# SCH_Moses-Mini_2025-01-24.net
KiCad netlist of a schematic drawn in EasyEDA
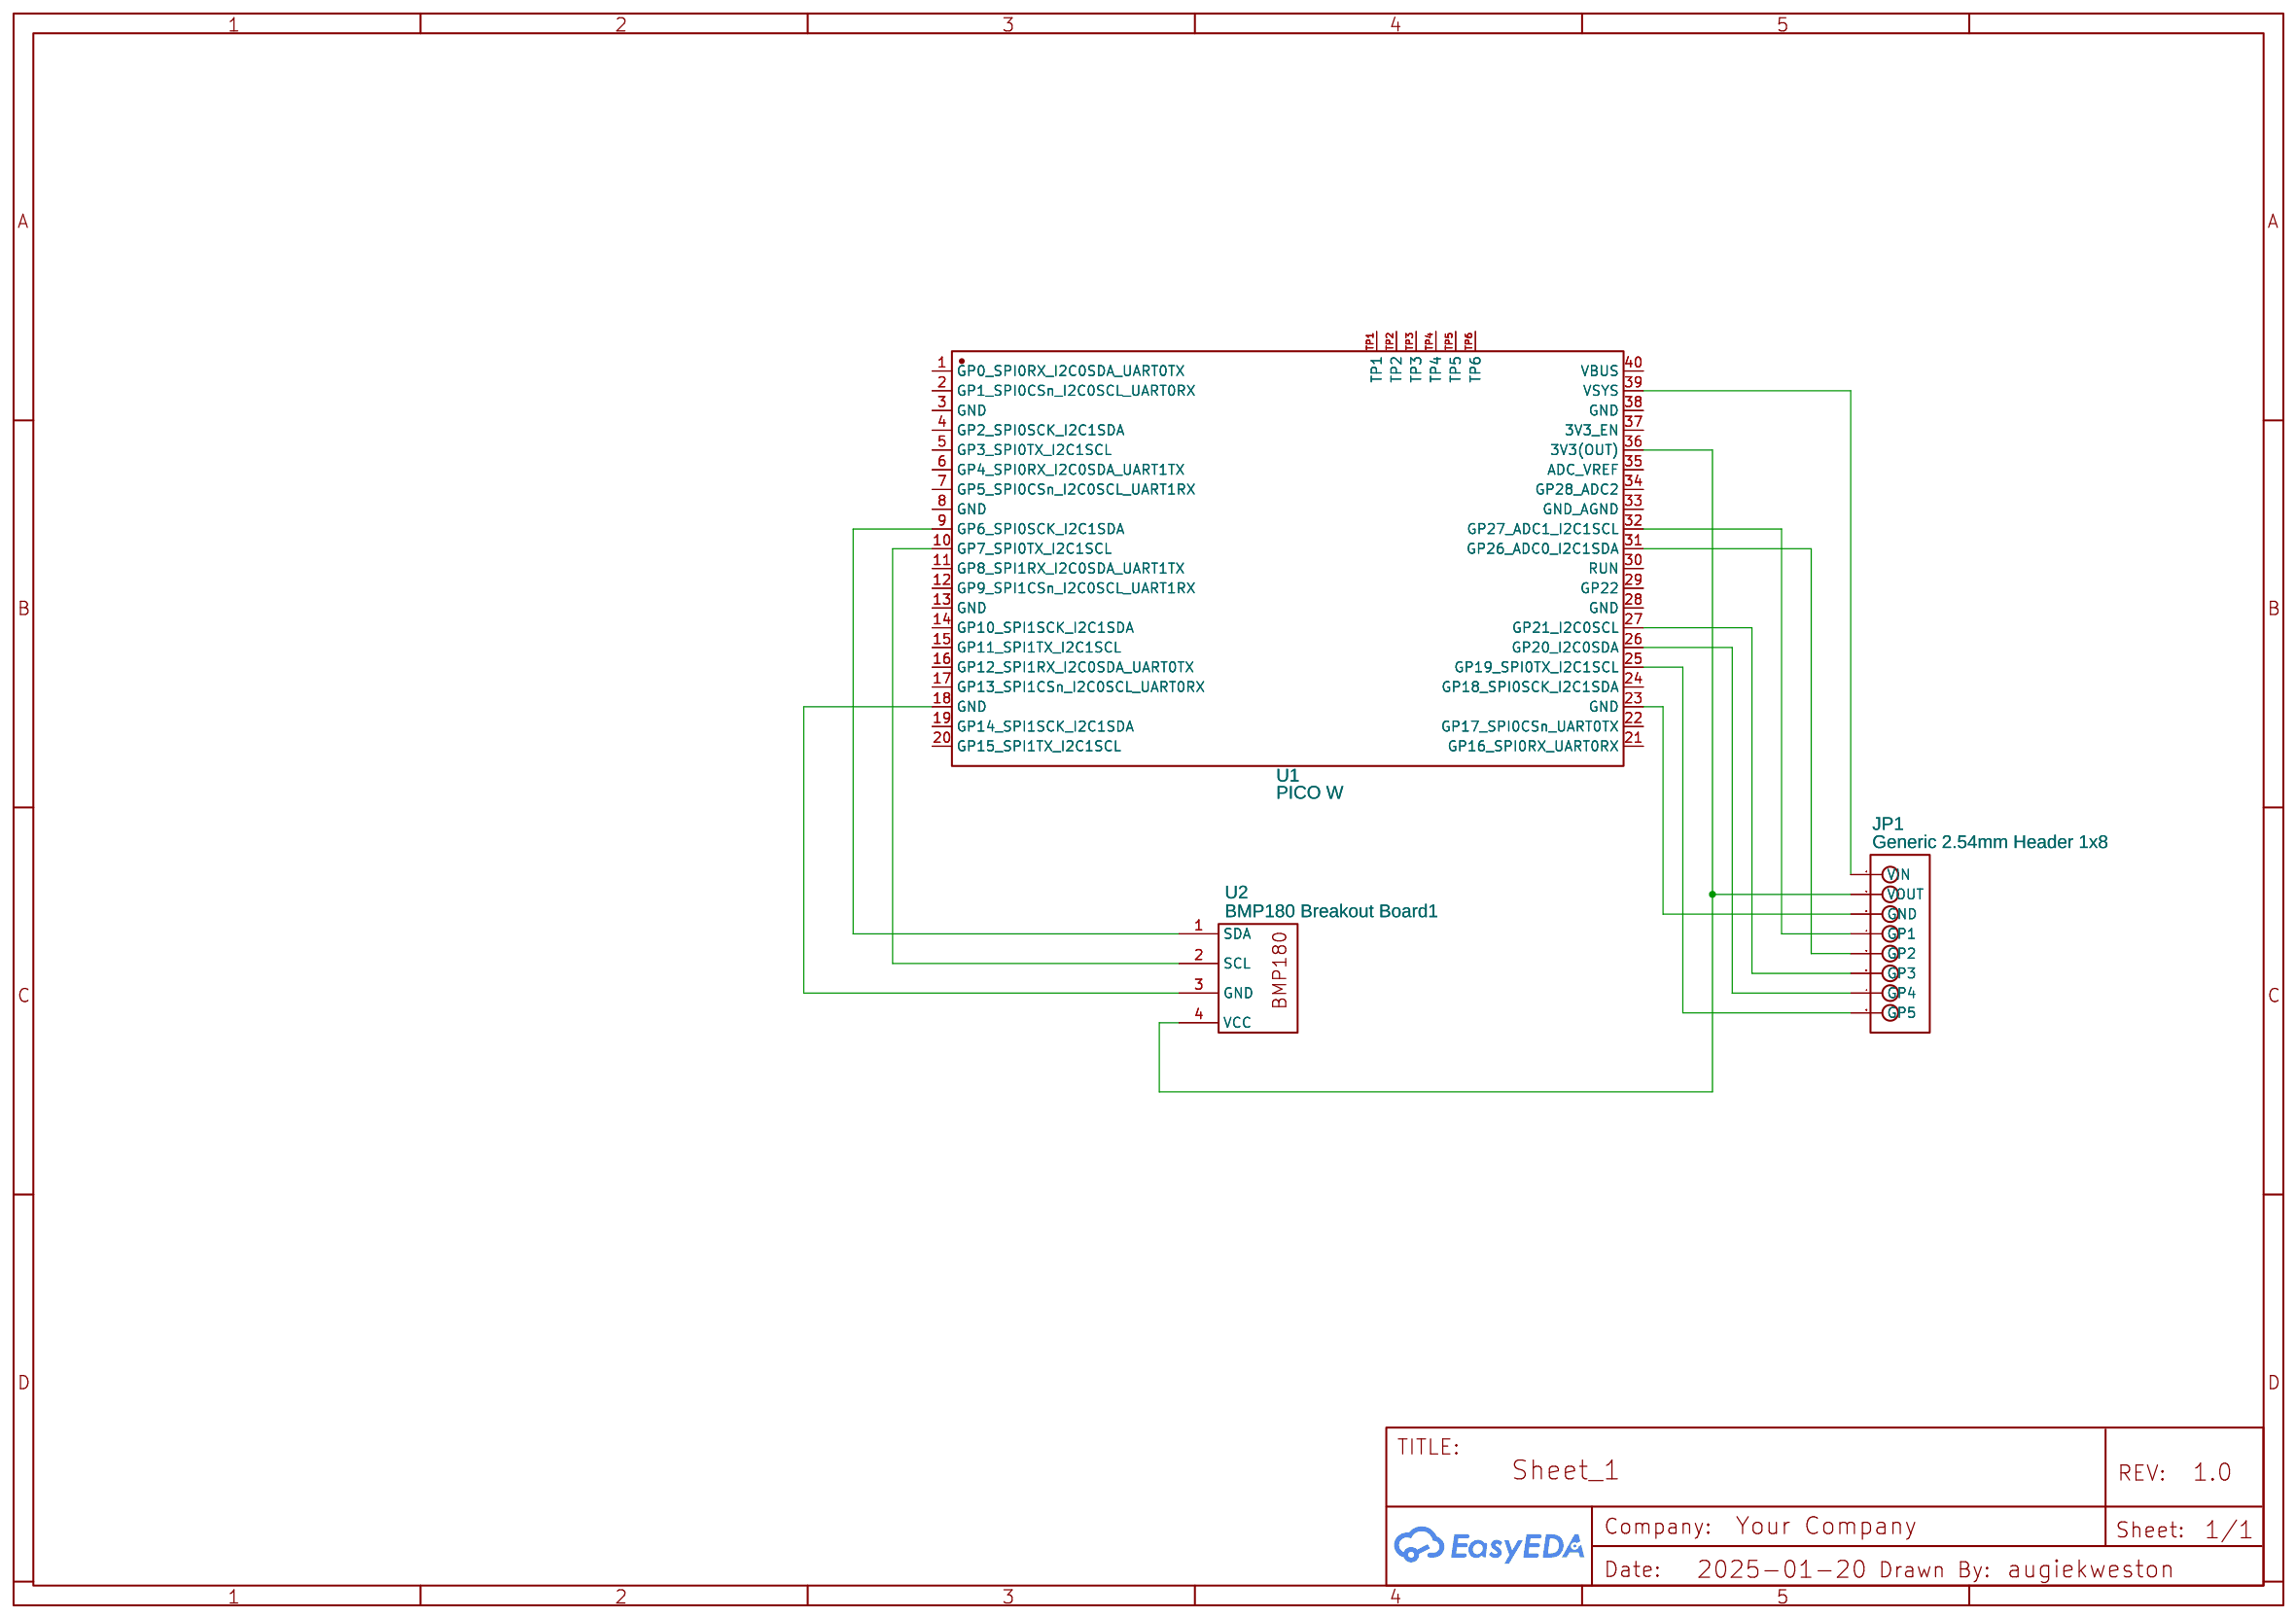
[diagram p0: schematic sheet]

(export (version "E")
  (design (tool "Eeschema 10.0.6"))
  (components
    (comp (ref "JP1")
      (value "Generic 2.54mm Header 1x8")
      (libsource (lib "") (part "Generic 2.54mm Header 1x8"))
    )
    (comp (ref "U1")
      (value "PICO W")
      (fields (field (name "Manufacturer") "Raspberry Pi(树莓派)"))
      (libsource (lib "") (part "PICO W"))
    )
    (comp (ref "U2") (value "BMP180 Breakout Board1") (libsource (lib "") (part "BMP180 Breakout Board1")))
  )
  (nets
    (net (code "1") (name "Net-(JP1-GND)") (class "Default")
      (node (ref "JP1") (pin "3") (pinfunction "GND_3") (pintype "unspecified"))
      (node (ref "U1") (pin "23") (pinfunction "GND_23") (pintype "unspecified"))
    )
    (net (code "2") (name "Net-(JP1-GP1)") (class "Default")
      (node (ref "JP1") (pin "4") (pinfunction "GP1_4") (pintype "unspecified"))
      (node (ref "U1") (pin "32") (pinfunction "GP27_ADC1_I2C1SCL_32") (pintype "unspecified"))
    )
    (net (code "3") (name "Net-(JP1-GP2)") (class "Default")
      (node (ref "JP1") (pin "5") (pinfunction "GP2_5") (pintype "unspecified"))
      (node (ref "U1") (pin "31") (pinfunction "GP26_ADC0_I2C1SDA_31") (pintype "unspecified"))
    )
    (net (code "4") (name "Net-(JP1-GP3)") (class "Default")
      (node (ref "JP1") (pin "6") (pinfunction "GP3_6") (pintype "unspecified"))
      (node (ref "U1") (pin "27") (pinfunction "GP21_I2C0SCL_27") (pintype "unspecified"))
    )
    (net (code "5") (name "Net-(JP1-GP4)") (class "Default")
      (node (ref "JP1") (pin "7") (pinfunction "GP4_7") (pintype "unspecified"))
      (node (ref "U1") (pin "26") (pinfunction "GP20_I2C0SDA_26") (pintype "unspecified"))
    )
    (net (code "6") (name "Net-(JP1-GP5)") (class "Default")
      (node (ref "JP1") (pin "8") (pinfunction "GP5_8") (pintype "unspecified"))
      (node (ref "U1") (pin "25") (pinfunction "GP19_SPI0TX_I2C1SCL_25") (pintype "unspecified"))
    )
    (net (code "7") (name "Net-(JP1-VIN)") (class "Default")
      (node (ref "JP1") (pin "1") (pinfunction "VIN_1") (pintype "unspecified"))
      (node (ref "U1") (pin "39") (pinfunction "VSYS_39") (pintype "unspecified"))
    )
    (net (code "8") (name "Net-(JP1-VOUT)") (class "Default")
      (node (ref "JP1") (pin "2") (pinfunction "VOUT_2") (pintype "unspecified"))
      (node (ref "U1") (pin "36") (pinfunction "3V3(OUT)_36") (pintype "unspecified"))
      (node (ref "U2") (pin "4") (pinfunction "VCC_4") (pintype "unspecified"))
    )
    (net (code "9") (name "Net-(U1-GP6_SPI0SCK_I2C1SDA)") (class "Default")
      (node (ref "U1") (pin "9") (pinfunction "GP6_SPI0SCK_I2C1SDA_9") (pintype "unspecified"))
      (node (ref "U2") (pin "1") (pinfunction "SDA_1") (pintype "unspecified"))
    )
    (net (code "10") (name "Net-(U1-GP7_SPI0TX_I2C1SCL)") (class "Default")
      (node (ref "U1") (pin "10") (pinfunction "GP7_SPI0TX_I2C1SCL_10") (pintype "unspecified"))
      (node (ref "U2") (pin "2") (pinfunction "SCL_2") (pintype "unspecified"))
    )
    (net (code "11") (name "Net-(U2-GND)") (class "Default")
      (node (ref "U1") (pin "18") (pinfunction "GND_18") (pintype "unspecified"))
      (node (ref "U2") (pin "3") (pinfunction "GND_3") (pintype "unspecified"))
    )
    (net (code "12") (name "unconnected-(U1-3V3_EN-Pad37)") (class "Default")
      (node (ref "U1") (pin "37") (pinfunction "3V3_EN_37") (pintype "unspecified"))
    )
    (net (code "13") (name "unconnected-(U1-ADC_VREF-Pad35)") (class "Default")
      (node (ref "U1") (pin "35") (pinfunction "ADC_VREF_35") (pintype "unspecified"))
    )
    (net (code "14") (name "unconnected-(U1-GND-Pad3)") (class "Default")
      (node (ref "U1") (pin "3") (pinfunction "GND_3") (pintype "unspecified"))
    )
    (net (code "15") (name "unconnected-(U1-GND-Pad8)") (class "Default")
      (node (ref "U1") (pin "8") (pinfunction "GND_8") (pintype "unspecified"))
    )
    (net (code "16") (name "unconnected-(U1-GND-Pad13)") (class "Default")
      (node (ref "U1") (pin "13") (pinfunction "GND_13") (pintype "unspecified"))
    )
    (net (code "17") (name "unconnected-(U1-GND-Pad28)") (class "Default")
      (node (ref "U1") (pin "28") (pinfunction "GND_28") (pintype "unspecified"))
    )
    (net (code "18") (name "unconnected-(U1-GND-Pad38)") (class "Default")
      (node (ref "U1") (pin "38") (pinfunction "GND_38") (pintype "unspecified"))
    )
    (net (code "19") (name "unconnected-(U1-GND_AGND-Pad33)") (class "Default")
      (node (ref "U1") (pin "33") (pinfunction "GND_AGND_33") (pintype "unspecified"))
    )
    (net (code "20") (name "unconnected-(U1-GP0_SPI0RX_I2C0SDA_UART0TX-Pad1)") (class "Default")
      (node (ref "U1") (pin "1") (pinfunction "GP0_SPI0RX_I2C0SDA_UART0TX_1") (pintype "unspecified"))
    )
    (net (code "21") (name "unconnected-(U1-GP1_SPI0CSn_I2C0SCL_UART0RX-Pad2)") (class "Default")
      (node (ref "U1") (pin "2") (pinfunction "GP1_SPI0CSn_I2C0SCL_UART0RX_2") (pintype "unspecified"))
    )
    (net (code "22") (name "unconnected-(U1-GP2_SPI0SCK_I2C1SDA-Pad4)") (class "Default")
      (node (ref "U1") (pin "4") (pinfunction "GP2_SPI0SCK_I2C1SDA_4") (pintype "unspecified"))
    )
    (net (code "23") (name "unconnected-(U1-GP3_SPI0TX_I2C1SCL-Pad5)") (class "Default")
      (node (ref "U1") (pin "5") (pinfunction "GP3_SPI0TX_I2C1SCL_5") (pintype "unspecified"))
    )
    (net (code "24") (name "unconnected-(U1-GP4_SPI0RX_I2C0SDA_UART1TX-Pad6)") (class "Default")
      (node (ref "U1") (pin "6") (pinfunction "GP4_SPI0RX_I2C0SDA_UART1TX_6") (pintype "unspecified"))
    )
    (net (code "25") (name "unconnected-(U1-GP5_SPI0CSn_I2C0SCL_UART1RX-Pad7)") (class "Default")
      (node (ref "U1") (pin "7") (pinfunction "GP5_SPI0CSn_I2C0SCL_UART1RX_7") (pintype "unspecified"))
    )
    (net (code "26") (name "unconnected-(U1-GP8_SPI1RX_I2C0SDA_UART1TX-Pad11)") (class "Default")
      (node (ref "U1") (pin "11") (pinfunction "GP8_SPI1RX_I2C0SDA_UART1TX_11") (pintype "unspecified"))
    )
    (net (code "27") (name "unconnected-(U1-GP9_SPI1CSn_I2C0SCL_UART1RX-Pad12)") (class "Default")
      (node (ref "U1") (pin "12") (pinfunction "GP9_SPI1CSn_I2C0SCL_UART1RX_12") (pintype "unspecified"))
    )
    (net (code "28") (name "unconnected-(U1-GP10_SPI1SCK_I2C1SDA-Pad14)") (class "Default")
      (node (ref "U1") (pin "14") (pinfunction "GP10_SPI1SCK_I2C1SDA_14") (pintype "unspecified"))
    )
    (net (code "29") (name "unconnected-(U1-GP11_SPI1TX_I2C1SCL-Pad15)") (class "Default")
      (node (ref "U1") (pin "15") (pinfunction "GP11_SPI1TX_I2C1SCL_15") (pintype "unspecified"))
    )
    (net (code "30") (name "unconnected-(U1-GP12_SPI1RX_I2C0SDA_UART0TX-Pad16)") (class "Default")
      (node (ref "U1") (pin "16") (pinfunction "GP12_SPI1RX_I2C0SDA_UART0TX_16") (pintype "unspecified"))
    )
    (net (code "31") (name "unconnected-(U1-GP13_SPI1CSn_I2C0SCL_UART0RX-Pad17)") (class "Default")
      (node (ref "U1") (pin "17") (pinfunction "GP13_SPI1CSn_I2C0SCL_UART0RX_17") (pintype "unspecified"))
    )
    (net (code "32") (name "unconnected-(U1-GP14_SPI1SCK_I2C1SDA-Pad19)") (class "Default")
      (node (ref "U1") (pin "19") (pinfunction "GP14_SPI1SCK_I2C1SDA_19") (pintype "unspecified"))
    )
    (net (code "33") (name "unconnected-(U1-GP15_SPI1TX_I2C1SCL-Pad20)") (class "Default")
      (node (ref "U1") (pin "20") (pinfunction "GP15_SPI1TX_I2C1SCL_20") (pintype "unspecified"))
    )
    (net (code "34") (name "unconnected-(U1-GP16_SPI0RX_UART0RX-Pad21)") (class "Default")
      (node (ref "U1") (pin "21") (pinfunction "GP16_SPI0RX_UART0RX_21") (pintype "unspecified"))
    )
    (net (code "35") (name "unconnected-(U1-GP17_SPI0CSn_UART0TX-Pad22)") (class "Default")
      (node (ref "U1") (pin "22") (pinfunction "GP17_SPI0CSn_UART0TX_22") (pintype "unspecified"))
    )
    (net (code "36") (name "unconnected-(U1-GP18_SPI0SCK_I2C1SDA-Pad24)") (class "Default")
      (node (ref "U1") (pin "24") (pinfunction "GP18_SPI0SCK_I2C1SDA_24") (pintype "unspecified"))
    )
    (net (code "37") (name "unconnected-(U1-GP22-Pad29)") (class "Default")
      (node (ref "U1") (pin "29") (pinfunction "GP22_29") (pintype "unspecified"))
    )
    (net (code "38") (name "unconnected-(U1-GP28_ADC2-Pad34)") (class "Default")
      (node (ref "U1") (pin "34") (pinfunction "GP28_ADC2_34") (pintype "unspecified"))
    )
    (net (code "39") (name "unconnected-(U1-PadTP1)") (class "Default")
      (node (ref "U1") (pin "TP1") (pinfunction "TP1_TP1") (pintype "unspecified"))
    )
    (net (code "40") (name "unconnected-(U1-PadTP2)") (class "Default")
      (node (ref "U1") (pin "TP2") (pinfunction "TP2_TP2") (pintype "unspecified"))
    )
    (net (code "41") (name "unconnected-(U1-PadTP3)") (class "Default")
      (node (ref "U1") (pin "TP3") (pinfunction "TP3_TP3") (pintype "unspecified"))
    )
    (net (code "42") (name "unconnected-(U1-PadTP4)") (class "Default")
      (node (ref "U1") (pin "TP4") (pinfunction "TP4_TP4") (pintype "unspecified"))
    )
    (net (code "43") (name "unconnected-(U1-PadTP5)") (class "Default")
      (node (ref "U1") (pin "TP5") (pinfunction "TP5_TP5") (pintype "unspecified"))
    )
    (net (code "44") (name "unconnected-(U1-PadTP6)") (class "Default")
      (node (ref "U1") (pin "TP6") (pinfunction "TP6_TP6") (pintype "unspecified"))
    )
    (net (code "45") (name "unconnected-(U1-RUN-Pad30)") (class "Default")
      (node (ref "U1") (pin "30") (pinfunction "RUN_30") (pintype "unspecified"))
    )
    (net (code "46") (name "unconnected-(U1-VBUS-Pad40)") (class "Default")
      (node (ref "U1") (pin "40") (pinfunction "VBUS_40") (pintype "unspecified"))
    )
  )
)
